# sensorboard.net
KiCad netlist of a schematic drawn in EAGLE
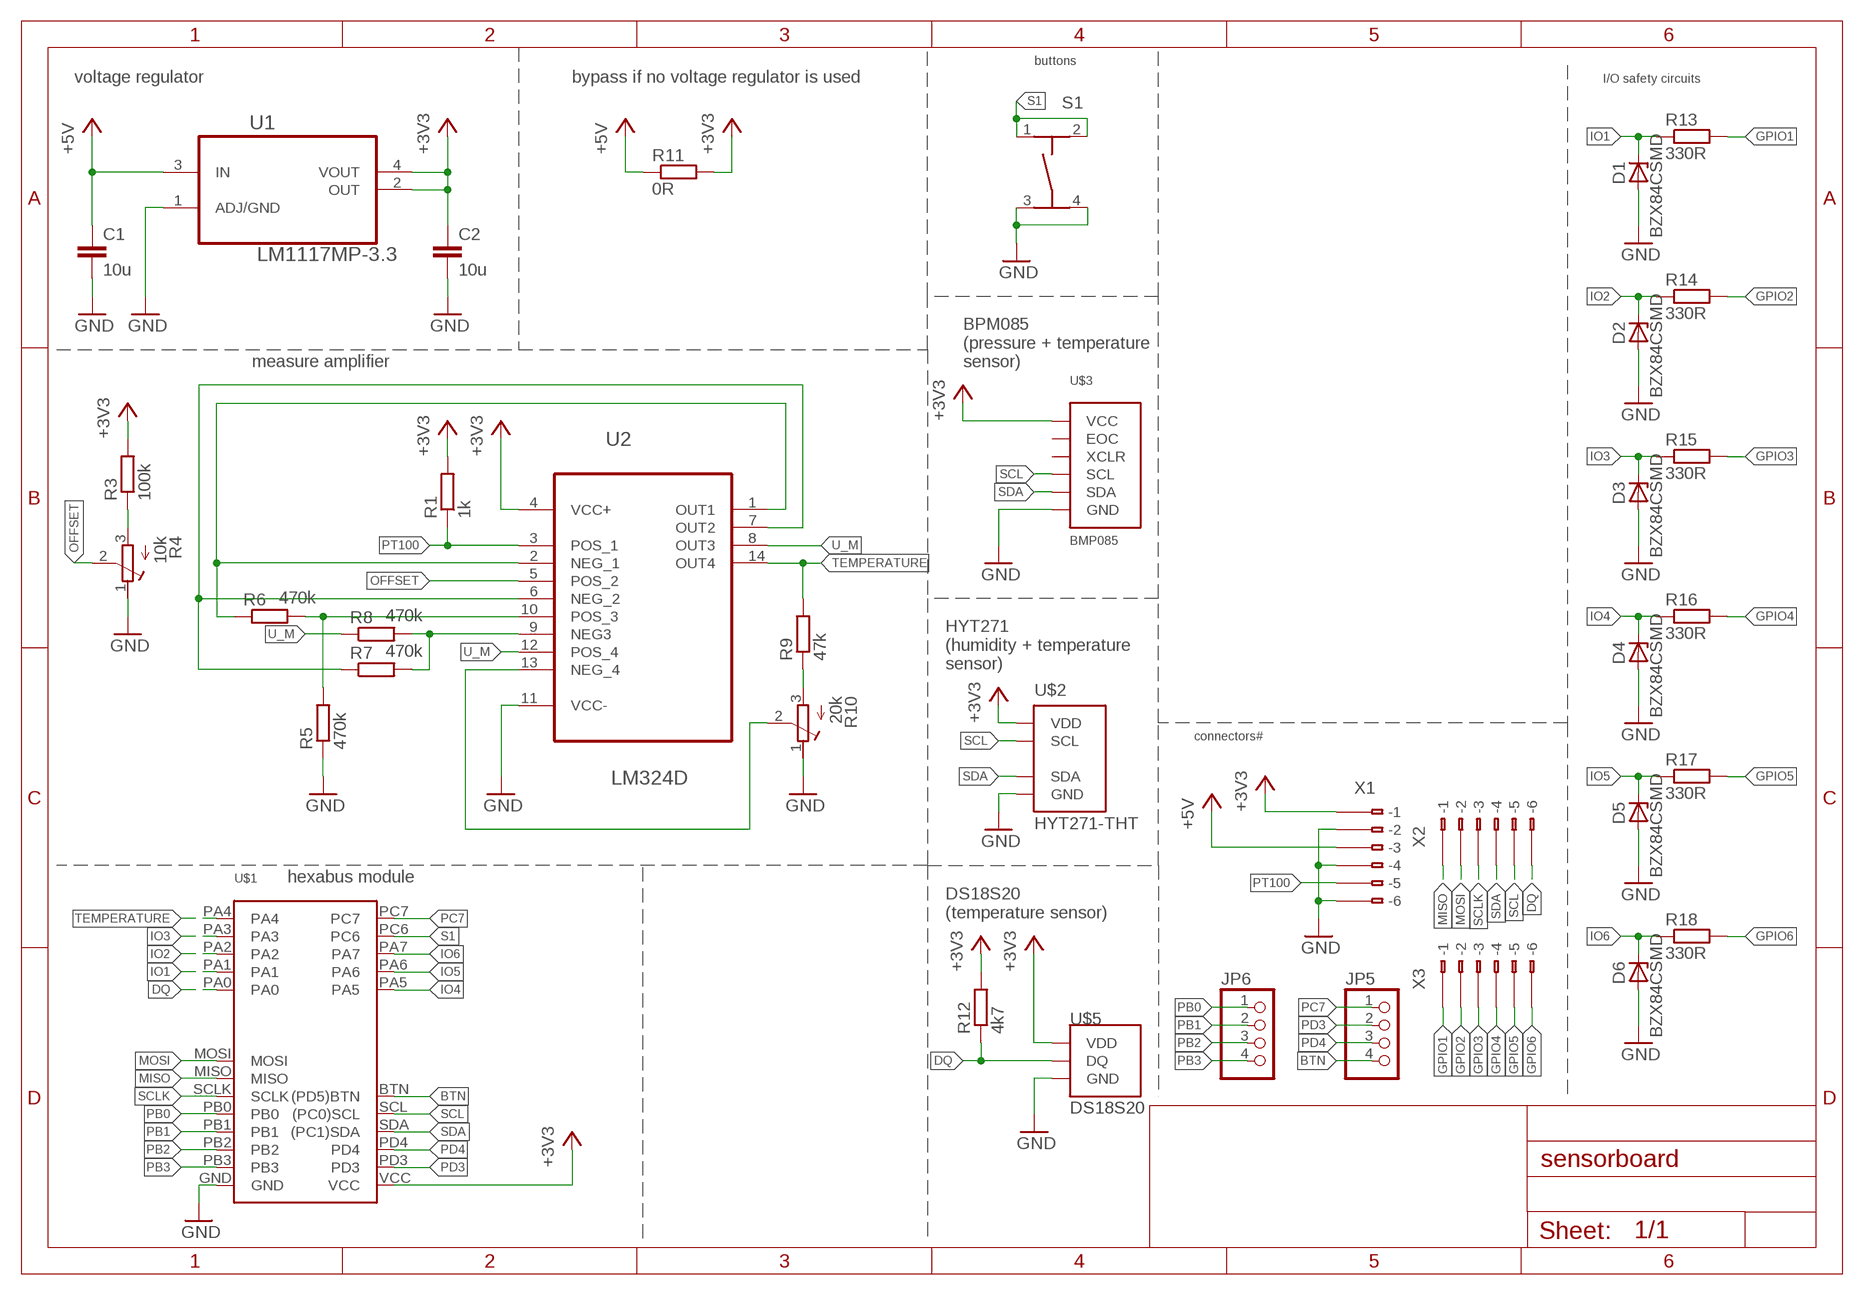
[diagram p0: schematic, sheet 1]

(export (version "E")
  (design (tool "Eeschema 10.0.6"))
  (components
    (comp (ref "C1")
      (value "10u")
      (footprint "eagle-import:C0805")
      (libsource (lib "eagle-import") (part "C-EUC0805"))
    )
    (comp (ref "C2")
      (value "10u")
      (footprint "eagle-import:C0805")
      (libsource (lib "eagle-import") (part "C-EUC0805"))
    )
    (comp (ref "D1")
      (value "BZX84CSMD")
      (footprint "eagle-import:TO236")
      (libsource (lib "eagle-import") (part "BZX84CSMD"))
    )
    (comp (ref "D2")
      (value "BZX84CSMD")
      (footprint "eagle-import:TO236")
      (libsource (lib "eagle-import") (part "BZX84CSMD"))
    )
    (comp (ref "D3")
      (value "BZX84CSMD")
      (footprint "eagle-import:TO236")
      (libsource (lib "eagle-import") (part "BZX84CSMD"))
    )
    (comp (ref "D4")
      (value "BZX84CSMD")
      (footprint "eagle-import:TO236")
      (libsource (lib "eagle-import") (part "BZX84CSMD"))
    )
    (comp (ref "D5")
      (value "BZX84CSMD")
      (footprint "eagle-import:TO236")
      (libsource (lib "eagle-import") (part "BZX84CSMD"))
    )
    (comp (ref "D6")
      (value "BZX84CSMD")
      (footprint "eagle-import:TO236")
      (libsource (lib "eagle-import") (part "BZX84CSMD"))
    )
    (comp (ref "JP5")
      (value "PINHD-1X4")
      (footprint "eagle-import:1X04")
      (libsource (lib "eagle-import") (part "PINHD-1X4"))
    )
    (comp (ref "JP6")
      (value "PINHD-1X4")
      (footprint "eagle-import:1X04")
      (libsource (lib "eagle-import") (part "PINHD-1X4"))
    )
    (comp (ref "R1")
      (value "1k")
      (footprint "eagle-import:R0805")
      (libsource (lib "eagle-import") (part "R-EU_R0805"))
    )
    (comp (ref "R3")
      (value "100k")
      (footprint "eagle-import:R0805")
      (libsource (lib "eagle-import") (part "R-EU_R0805"))
    )
    (comp (ref "R4")
      (value "10k")
      (footprint "eagle-import:RTRIMT93YB")
      (libsource (lib "eagle-import") (part "R-TRIMMT93YB"))
    )
    (comp (ref "R5")
      (value "470k")
      (footprint "eagle-import:R0805")
      (libsource (lib "eagle-import") (part "R-EU_R0805"))
    )
    (comp (ref "R6")
      (value "470k")
      (footprint "eagle-import:R0805")
      (libsource (lib "eagle-import") (part "R-EU_R0805"))
    )
    (comp (ref "R7")
      (value "470k")
      (footprint "eagle-import:R0805")
      (libsource (lib "eagle-import") (part "R-EU_R0805"))
    )
    (comp (ref "R8")
      (value "470k")
      (footprint "eagle-import:R0805")
      (libsource (lib "eagle-import") (part "R-EU_R0805"))
    )
    (comp (ref "R9")
      (value "47k")
      (footprint "eagle-import:R0805")
      (libsource (lib "eagle-import") (part "R-EU_R0805"))
    )
    (comp (ref "R10")
      (value "20k")
      (footprint "eagle-import:RTRIMT93YB")
      (libsource (lib "eagle-import") (part "R-TRIMMT93YB"))
    )
    (comp (ref "R11")
      (value "0R")
      (footprint "eagle-import:R0805")
      (libsource (lib "eagle-import") (part "R-EU_R0805"))
    )
    (comp (ref "R12")
      (value "4k7")
      (footprint "eagle-import:R0805")
      (libsource (lib "eagle-import") (part "R-EU_R0805"))
    )
    (comp (ref "R13")
      (value "330R")
      (footprint "eagle-import:R0805")
      (libsource (lib "eagle-import") (part "R-EU_R0805"))
    )
    (comp (ref "R14")
      (value "330R")
      (footprint "eagle-import:R0805")
      (libsource (lib "eagle-import") (part "R-EU_R0805"))
    )
    (comp (ref "R15")
      (value "330R")
      (footprint "eagle-import:R0805")
      (libsource (lib "eagle-import") (part "R-EU_R0805"))
    )
    (comp (ref "R16")
      (value "330R")
      (footprint "eagle-import:R0805")
      (libsource (lib "eagle-import") (part "R-EU_R0805"))
    )
    (comp (ref "R17")
      (value "330R")
      (footprint "eagle-import:R0805")
      (libsource (lib "eagle-import") (part "R-EU_R0805"))
    )
    (comp (ref "R18")
      (value "330R")
      (footprint "eagle-import:R0805")
      (libsource (lib "eagle-import") (part "R-EU_R0805"))
    )
    (comp (ref "S1")
      (value "TASTER-9314_SMD")
      (footprint "eagle-import:TASTER-9314_SMD")
      (libsource (lib "eagle-import") (part "TASTER-9314_SMD"))
    )
    (comp (ref "U$1")
      (value "HEXABUS")
      (footprint "eagle-import:HEXABUS")
      (libsource (lib "eagle-import") (part "HEXABUS"))
    )
    (comp (ref "U$2")
      (value "HYT271-THT")
      (footprint "eagle-import:HYT271-THT")
      (libsource (lib "eagle-import") (part "HYT271-THT"))
    )
    (comp (ref "U$3")
      (value "BMP085")
      (footprint "eagle-import:BREAKOUT")
      (libsource (lib "eagle-import") (part "BMP085"))
    )
    (comp (ref "U$5")
      (value "DS18S20")
      (footprint "eagle-import:TO-92")
      (libsource (lib "eagle-import") (part "DS18S20"))
    )
    (comp (ref "U1")
      (value "LM1117MP-3.3")
      (footprint "eagle-import:SOT230P696X180-4N")
      (libsource (lib "eagle-import") (part "LM1117MP-3.3"))
    )
    (comp (ref "U2")
      (value "LM324D")
      (footprint "eagle-import:SOIC127P600X175-14N")
      (libsource (lib "eagle-import") (part "LM324D"))
    )
    (comp (ref "X1")
      (value "233-206")
      (footprint "eagle-import:233-206")
      (libsource (lib "eagle-import") (part "233-206"))
    )
    (comp (ref "X2")
      (value "233-206")
      (footprint "eagle-import:233-206")
      (libsource (lib "eagle-import") (part "233-206"))
    )
    (comp (ref "X3")
      (value "233-206")
      (footprint "eagle-import:233-206")
      (libsource (lib "eagle-import") (part "233-206"))
    )
  )
  (nets
    (net (code "1") (name "+3V3") (class "Default")
      (node (ref "C2") (pin "1") (pinfunction "1_1") (pintype "passive"))
      (node (ref "R1") (pin "2") (pinfunction "2_2") (pintype "passive"))
      (node (ref "R11") (pin "2") (pinfunction "2_2") (pintype "passive"))
      (node (ref "R12") (pin "2") (pinfunction "2_2") (pintype "passive"))
      (node (ref "R3") (pin "2") (pinfunction "2_2") (pintype "passive"))
      (node (ref "U$1") (pin "VCC") (pinfunction "VCC_VCC") (pintype "bidirectional"))
      (node (ref "U$2") (pin "VDD") (pinfunction "VDD_VDD") (pintype "power_in"))
      (node (ref "U$3") (pin "VCC") (pinfunction "VCC_VCC") (pintype "bidirectional"))
      (node (ref "U$5") (pin "VDD") (pinfunction "VDD_VDD") (pintype "bidirectional"))
      (node (ref "U1") (pin "2") (pinfunction "OUT_2") (pintype "output"))
      (node (ref "U1") (pin "4") (pinfunction "VOUT_4") (pintype "output"))
      (node (ref "U2") (pin "4") (pinfunction "VCC+_4") (pintype "power_in"))
      (node (ref "X1") (pin "B1") (pinfunction "B-1_B1") (pintype "passive"))
    )
    (net (code "2") (name "+5V") (class "Default")
      (node (ref "C1") (pin "1") (pinfunction "1_1") (pintype "passive"))
      (node (ref "R11") (pin "1") (pinfunction "1_1") (pintype "passive"))
      (node (ref "U1") (pin "3") (pinfunction "IN_3") (pintype "input"))
      (node (ref "X1") (pin "B3") (pinfunction "B-3_B3") (pintype "passive"))
    )
    (net (code "3") (name "BTN") (class "Default")
      (node (ref "JP5") (pin "4") (pinfunction "4_4") (pintype "passive"))
      (node (ref "U$1") (pin "BTN") (pinfunction "(PD5)BTN_BTN") (pintype "bidirectional"))
    )
    (net (code "4") (name "DQ") (class "Default")
      (node (ref "R12") (pin "1") (pinfunction "1_1") (pintype "passive"))
      (node (ref "U$1") (pin "PA0") (pinfunction "PA0_PA0") (pintype "bidirectional"))
      (node (ref "U$5") (pin "DQ") (pinfunction "DQ_DQ") (pintype "bidirectional"))
      (node (ref "X2") (pin "B6") (pinfunction "B-6_B6") (pintype "passive"))
    )
    (net (code "5") (name "GND") (class "Default")
      (node (ref "C1") (pin "2") (pinfunction "2_2") (pintype "passive"))
      (node (ref "C2") (pin "2") (pinfunction "2_2") (pintype "passive"))
      (node (ref "D1") (pin "A") (pinfunction "A_A") (pintype "passive"))
      (node (ref "D2") (pin "A") (pinfunction "A_A") (pintype "passive"))
      (node (ref "D3") (pin "A") (pinfunction "A_A") (pintype "passive"))
      (node (ref "D4") (pin "A") (pinfunction "A_A") (pintype "passive"))
      (node (ref "D5") (pin "A") (pinfunction "A_A") (pintype "passive"))
      (node (ref "D6") (pin "A") (pinfunction "A_A") (pintype "passive"))
      (node (ref "R10") (pin "1") (pinfunction "E_1") (pintype "passive"))
      (node (ref "R4") (pin "1") (pinfunction "E_1") (pintype "passive"))
      (node (ref "R5") (pin "1") (pinfunction "1_1") (pintype "passive"))
      (node (ref "S1") (pin "3") (pinfunction "3_3") (pintype "passive"))
      (node (ref "S1") (pin "4") (pinfunction "4_4") (pintype "passive"))
      (node (ref "U$1") (pin "GND") (pinfunction "GND_GND") (pintype "bidirectional"))
      (node (ref "U$2") (pin "GND") (pinfunction "GND_GND") (pintype "power_in"))
      (node (ref "U$3") (pin "GND") (pinfunction "GND_GND") (pintype "bidirectional"))
      (node (ref "U$5") (pin "GND") (pinfunction "GND_GND") (pintype "bidirectional"))
      (node (ref "U1") (pin "1") (pinfunction "ADJ/GND_1") (pintype "passive"))
      (node (ref "U2") (pin "11") (pinfunction "VCC-_11") (pintype "power_in"))
      (node (ref "X1") (pin "B2") (pinfunction "B-2_B2") (pintype "passive"))
      (node (ref "X1") (pin "B4") (pinfunction "B-4_B4") (pintype "passive"))
      (node (ref "X1") (pin "B6") (pinfunction "B-6_B6") (pintype "passive"))
    )
    (net (code "6") (name "GPIO1") (class "Default")
      (node (ref "R13") (pin "2") (pinfunction "2_2") (pintype "passive"))
      (node (ref "X3") (pin "B1") (pinfunction "B-1_B1") (pintype "passive"))
    )
    (net (code "7") (name "GPIO2") (class "Default")
      (node (ref "R14") (pin "2") (pinfunction "2_2") (pintype "passive"))
      (node (ref "X3") (pin "B2") (pinfunction "B-2_B2") (pintype "passive"))
    )
    (net (code "8") (name "GPIO3") (class "Default")
      (node (ref "R15") (pin "2") (pinfunction "2_2") (pintype "passive"))
      (node (ref "X3") (pin "B3") (pinfunction "B-3_B3") (pintype "passive"))
    )
    (net (code "9") (name "GPIO4") (class "Default")
      (node (ref "R16") (pin "2") (pinfunction "2_2") (pintype "passive"))
      (node (ref "X3") (pin "B4") (pinfunction "B-4_B4") (pintype "passive"))
    )
    (net (code "10") (name "GPIO5") (class "Default")
      (node (ref "R17") (pin "2") (pinfunction "2_2") (pintype "passive"))
      (node (ref "X3") (pin "B5") (pinfunction "B-5_B5") (pintype "passive"))
    )
    (net (code "11") (name "GPIO6") (class "Default")
      (node (ref "R18") (pin "2") (pinfunction "2_2") (pintype "passive"))
      (node (ref "X3") (pin "B6") (pinfunction "B-6_B6") (pintype "passive"))
    )
    (net (code "12") (name "IO1") (class "Default")
      (node (ref "D1") (pin "C") (pinfunction "C_C") (pintype "passive"))
      (node (ref "R13") (pin "1") (pinfunction "1_1") (pintype "passive"))
      (node (ref "U$1") (pin "PA1") (pinfunction "PA1_PA1") (pintype "bidirectional"))
    )
    (net (code "13") (name "IO2") (class "Default")
      (node (ref "D2") (pin "C") (pinfunction "C_C") (pintype "passive"))
      (node (ref "R14") (pin "1") (pinfunction "1_1") (pintype "passive"))
      (node (ref "U$1") (pin "PA2") (pinfunction "PA2_PA2") (pintype "bidirectional"))
    )
    (net (code "14") (name "IO3") (class "Default")
      (node (ref "D3") (pin "C") (pinfunction "C_C") (pintype "passive"))
      (node (ref "R15") (pin "1") (pinfunction "1_1") (pintype "passive"))
      (node (ref "U$1") (pin "PA3") (pinfunction "PA3_PA3") (pintype "bidirectional"))
    )
    (net (code "15") (name "IO4") (class "Default")
      (node (ref "D4") (pin "C") (pinfunction "C_C") (pintype "passive"))
      (node (ref "R16") (pin "1") (pinfunction "1_1") (pintype "passive"))
      (node (ref "U$1") (pin "PA5") (pinfunction "PA5_PA5") (pintype "bidirectional"))
    )
    (net (code "16") (name "IO5") (class "Default")
      (node (ref "D5") (pin "C") (pinfunction "C_C") (pintype "passive"))
      (node (ref "R17") (pin "1") (pinfunction "1_1") (pintype "passive"))
      (node (ref "U$1") (pin "PA6") (pinfunction "PA6_PA6") (pintype "bidirectional"))
    )
    (net (code "17") (name "IO6") (class "Default")
      (node (ref "D6") (pin "C") (pinfunction "C_C") (pintype "passive"))
      (node (ref "R18") (pin "1") (pinfunction "1_1") (pintype "passive"))
      (node (ref "U$1") (pin "PA7") (pinfunction "PA7_PA7") (pintype "bidirectional"))
    )
    (net (code "18") (name "MISO") (class "Default")
      (node (ref "U$1") (pin "MISO") (pinfunction "MISO_MISO") (pintype "bidirectional"))
      (node (ref "X2") (pin "B1") (pinfunction "B-1_B1") (pintype "passive"))
    )
    (net (code "19") (name "MOSI") (class "Default")
      (node (ref "U$1") (pin "MOSI") (pinfunction "MOSI_MOSI") (pintype "bidirectional"))
      (node (ref "X2") (pin "B2") (pinfunction "B-2_B2") (pintype "passive"))
    )
    (net (code "20") (name "Net-(R4-A)") (class "Default")
      (node (ref "R3") (pin "1") (pinfunction "1_1") (pintype "passive"))
      (node (ref "R4") (pin "3") (pinfunction "A_3") (pintype "passive"))
    )
    (net (code "21") (name "Net-(R10-A)") (class "Default")
      (node (ref "R10") (pin "3") (pinfunction "A_3") (pintype "passive"))
      (node (ref "R9") (pin "1") (pinfunction "1_1") (pintype "passive"))
    )
    (net (code "22") (name "Net-(R10-S)") (class "Default")
      (node (ref "R10") (pin "2") (pinfunction "S_2") (pintype "passive"))
      (node (ref "U2") (pin "13") (pinfunction "NEG_4_13") (pintype "input"))
    )
    (net (code "23") (name "Net-(U2-NEG3)") (class "Default")
      (node (ref "R7") (pin "2") (pinfunction "2_2") (pintype "passive"))
      (node (ref "R8") (pin "2") (pinfunction "2_2") (pintype "passive"))
      (node (ref "U2") (pin "9") (pinfunction "NEG3_9") (pintype "input"))
    )
    (net (code "24") (name "Net-(U2-NEG_1)") (class "Default")
      (node (ref "R6") (pin "1") (pinfunction "1_1") (pintype "passive"))
      (node (ref "U2") (pin "1") (pinfunction "OUT1_1") (pintype "output"))
      (node (ref "U2") (pin "2") (pinfunction "NEG_1_2") (pintype "input"))
    )
    (net (code "25") (name "Net-(U2-NEG_2)") (class "Default")
      (node (ref "R7") (pin "1") (pinfunction "1_1") (pintype "passive"))
      (node (ref "U2") (pin "6") (pinfunction "NEG_2_6") (pintype "input"))
      (node (ref "U2") (pin "7") (pinfunction "OUT2_7") (pintype "output"))
    )
    (net (code "26") (name "Net-(U2-POS_3)") (class "Default")
      (node (ref "R5") (pin "2") (pinfunction "2_2") (pintype "passive"))
      (node (ref "R6") (pin "2") (pinfunction "2_2") (pintype "passive"))
      (node (ref "U2") (pin "10") (pinfunction "POS_3_10") (pintype "input"))
    )
    (net (code "27") (name "OFFSET") (class "Default")
      (node (ref "R4") (pin "2") (pinfunction "S_2") (pintype "passive"))
      (node (ref "U2") (pin "5") (pinfunction "POS_2_5") (pintype "input"))
    )
    (net (code "28") (name "PB0") (class "Default")
      (node (ref "JP6") (pin "1") (pinfunction "1_1") (pintype "passive"))
      (node (ref "U$1") (pin "PB0") (pinfunction "PB0_PB0") (pintype "bidirectional"))
    )
    (net (code "29") (name "PB1") (class "Default")
      (node (ref "JP6") (pin "2") (pinfunction "2_2") (pintype "passive"))
      (node (ref "U$1") (pin "PB1") (pinfunction "PB1_PB1") (pintype "bidirectional"))
    )
    (net (code "30") (name "PB2") (class "Default")
      (node (ref "JP6") (pin "3") (pinfunction "3_3") (pintype "passive"))
      (node (ref "U$1") (pin "PB2") (pinfunction "PB2_PB2") (pintype "bidirectional"))
    )
    (net (code "31") (name "PB3") (class "Default")
      (node (ref "JP6") (pin "4") (pinfunction "4_4") (pintype "passive"))
      (node (ref "U$1") (pin "PB3") (pinfunction "PB3_PB3") (pintype "bidirectional"))
    )
    (net (code "32") (name "PC7") (class "Default")
      (node (ref "JP5") (pin "1") (pinfunction "1_1") (pintype "passive"))
      (node (ref "U$1") (pin "PC7") (pinfunction "PC7_PC7") (pintype "bidirectional"))
    )
    (net (code "33") (name "PD3") (class "Default")
      (node (ref "JP5") (pin "2") (pinfunction "2_2") (pintype "passive"))
      (node (ref "U$1") (pin "PD3") (pinfunction "PD3_PD3") (pintype "bidirectional"))
    )
    (net (code "34") (name "PD4") (class "Default")
      (node (ref "JP5") (pin "3") (pinfunction "3_3") (pintype "passive"))
      (node (ref "U$1") (pin "PD4") (pinfunction "PD4_PD4") (pintype "bidirectional"))
    )
    (net (code "35") (name "PT100") (class "Default")
      (node (ref "R1") (pin "1") (pinfunction "1_1") (pintype "passive"))
      (node (ref "U2") (pin "3") (pinfunction "POS_1_3") (pintype "input"))
      (node (ref "X1") (pin "B5") (pinfunction "B-5_B5") (pintype "passive"))
    )
    (net (code "36") (name "S1") (class "Default")
      (node (ref "S1") (pin "1") (pinfunction "1_1") (pintype "passive"))
      (node (ref "S1") (pin "2") (pinfunction "2_2") (pintype "passive"))
      (node (ref "U$1") (pin "PC6") (pinfunction "PC6_PC6") (pintype "bidirectional"))
    )
    (net (code "37") (name "SCL") (class "Default")
      (node (ref "U$1") (pin "SCL") (pinfunction "(PC0)SCL_SCL") (pintype "bidirectional"))
      (node (ref "U$2") (pin "SCL") (pinfunction "SCL_SCL") (pintype "bidirectional"))
      (node (ref "U$3") (pin "SCL") (pinfunction "SCL_SCL") (pintype "bidirectional"))
      (node (ref "X2") (pin "B5") (pinfunction "B-5_B5") (pintype "passive"))
    )
    (net (code "38") (name "SCLK") (class "Default")
      (node (ref "U$1") (pin "SCLK") (pinfunction "SCLK_SCLK") (pintype "bidirectional"))
      (node (ref "X2") (pin "B3") (pinfunction "B-3_B3") (pintype "passive"))
    )
    (net (code "39") (name "SDA") (class "Default")
      (node (ref "U$1") (pin "SDA") (pinfunction "(PC1)SDA_SDA") (pintype "bidirectional"))
      (node (ref "U$2") (pin "SDA") (pinfunction "SDA_SDA") (pintype "bidirectional"))
      (node (ref "U$3") (pin "SDA") (pinfunction "SDA_SDA") (pintype "bidirectional"))
      (node (ref "X2") (pin "B4") (pinfunction "B-4_B4") (pintype "passive"))
    )
    (net (code "40") (name "TEMPERATURE") (class "Default")
      (node (ref "R9") (pin "2") (pinfunction "2_2") (pintype "passive"))
      (node (ref "U$1") (pin "PA4") (pinfunction "PA4_PA4") (pintype "bidirectional"))
      (node (ref "U2") (pin "14") (pinfunction "OUT4_14") (pintype "output"))
    )
    (net (code "41") (name "U_M") (class "Default")
      (node (ref "R8") (pin "1") (pinfunction "1_1") (pintype "passive"))
      (node (ref "U2") (pin "12") (pinfunction "POS_4_12") (pintype "input"))
      (node (ref "U2") (pin "8") (pinfunction "OUT3_8") (pintype "output"))
    )
    (net (code "42") (name "unconnected-(U$3-PadEOC)") (class "Default")
      (node (ref "U$3") (pin "EOC") (pinfunction "EOC_EOC") (pintype "bidirectional"))
    )
    (net (code "43") (name "unconnected-(U$3-PadXCLR)") (class "Default")
      (node (ref "U$3") (pin "XCLR") (pinfunction "XCLR_XCLR") (pintype "bidirectional"))
    )
    (net (code "44") (name "unconnected-(X1--1-PadA1)") (class "Default")
      (node (ref "X1") (pin "A1") (pinfunction "-1_A1") (pintype "passive"))
    )
    (net (code "45") (name "unconnected-(X1--2-PadA2)") (class "Default")
      (node (ref "X1") (pin "A2") (pinfunction "-2_A2") (pintype "passive"))
    )
    (net (code "46") (name "unconnected-(X1--3-PadA3)") (class "Default")
      (node (ref "X1") (pin "A3") (pinfunction "-3_A3") (pintype "passive"))
    )
    (net (code "47") (name "unconnected-(X1--4-PadA4)") (class "Default")
      (node (ref "X1") (pin "A4") (pinfunction "-4_A4") (pintype "passive"))
    )
    (net (code "48") (name "unconnected-(X1--5-PadA5)") (class "Default")
      (node (ref "X1") (pin "A5") (pinfunction "-5_A5") (pintype "passive"))
    )
    (net (code "49") (name "unconnected-(X1--6-PadA6)") (class "Default")
      (node (ref "X1") (pin "A6") (pinfunction "-6_A6") (pintype "passive"))
    )
    (net (code "50") (name "unconnected-(X2--1-PadA1)") (class "Default")
      (node (ref "X2") (pin "A1") (pinfunction "-1_A1") (pintype "passive"))
    )
    (net (code "51") (name "unconnected-(X2--2-PadA2)") (class "Default")
      (node (ref "X2") (pin "A2") (pinfunction "-2_A2") (pintype "passive"))
    )
    (net (code "52") (name "unconnected-(X2--3-PadA3)") (class "Default")
      (node (ref "X2") (pin "A3") (pinfunction "-3_A3") (pintype "passive"))
    )
    (net (code "53") (name "unconnected-(X2--4-PadA4)") (class "Default")
      (node (ref "X2") (pin "A4") (pinfunction "-4_A4") (pintype "passive"))
    )
    (net (code "54") (name "unconnected-(X2--5-PadA5)") (class "Default")
      (node (ref "X2") (pin "A5") (pinfunction "-5_A5") (pintype "passive"))
    )
    (net (code "55") (name "unconnected-(X2--6-PadA6)") (class "Default")
      (node (ref "X2") (pin "A6") (pinfunction "-6_A6") (pintype "passive"))
    )
    (net (code "56") (name "unconnected-(X3--1-PadA1)") (class "Default")
      (node (ref "X3") (pin "A1") (pinfunction "-1_A1") (pintype "passive"))
    )
    (net (code "57") (name "unconnected-(X3--2-PadA2)") (class "Default")
      (node (ref "X3") (pin "A2") (pinfunction "-2_A2") (pintype "passive"))
    )
    (net (code "58") (name "unconnected-(X3--3-PadA3)") (class "Default")
      (node (ref "X3") (pin "A3") (pinfunction "-3_A3") (pintype "passive"))
    )
    (net (code "59") (name "unconnected-(X3--4-PadA4)") (class "Default")
      (node (ref "X3") (pin "A4") (pinfunction "-4_A4") (pintype "passive"))
    )
    (net (code "60") (name "unconnected-(X3--5-PadA5)") (class "Default")
      (node (ref "X3") (pin "A5") (pinfunction "-5_A5") (pintype "passive"))
    )
    (net (code "61") (name "unconnected-(X3--6-PadA6)") (class "Default")
      (node (ref "X3") (pin "A6") (pinfunction "-6_A6") (pintype "passive"))
    )
  )
)
